# I2C-EXPANDER.net
KiCad netlist of a schematic drawn in Altium Designer
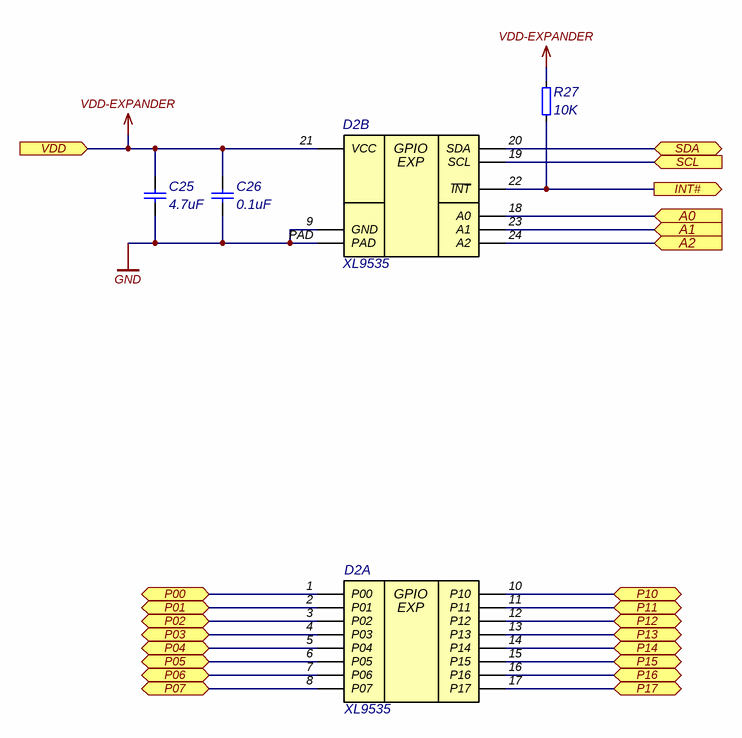
[diagram p0: I2C-EXPANDER.SchDoc]

(export (version "E")
  (design (tool "Eeschema 10.0.6"))
  (components
    (comp (ref "C25")
      (value "4.7uF")
      (footprint "C0402")
      (fields
        (field (name "PART NUMBER") "0402-X5R-6.3V-4.7uF±20%")
        (field (name "VOLTAGE") "6.3V")
        (field (name "TOLERANCE") "20%")
      )
      (libsource (lib "ATB") (part "C"))
    )
    (comp (ref "C26")
      (value "0.1uF")
      (footprint "C0402")
      (fields
        (field (name "PART NUMBER") "0402-X7R-16V-0.1uF±10%")
        (field (name "VOLTAGE") "16V")
        (field (name "TOLERANCE") "5%")
      )
      (libsource (lib "ATB") (part "C"))
    )
    (comp (ref "D2")
      (value "XL9535")
      (footprint "QFN_24_4X4_E0p5")
      (description "I2C  I/O Expander 16 bit")
      (fields (field (name "PART NUMBER") "XL9535QF24") (field (name "MANUFACTURER") "XINLUDA"))
      (libsource (lib "ATB") (part "XL95x5QF24"))
    )
    (comp (ref "R27")
      (value "10K")
      (footprint "R_0402")
      (fields
        (field (name "PART NUMBER") "0402-0.0625W-10K-100ppm±1%")
        (field (name "TOLERANCE") "1%")
        (field (name "MANUFACTURER") "Yageo")
      )
      (libsource (lib "ATB") (part "R"))
    )
  )
  (nets
    (net (code "1") (name "/A0") (class "Default")
      (node (ref "D2") (pin "18") (pinfunction "A0_18") (pintype "passive"))
    )
    (net (code "2") (name "/A1") (class "Default")
      (node (ref "D2") (pin "23") (pinfunction "A1_23") (pintype "passive"))
    )
    (net (code "3") (name "/A2") (class "Default")
      (node (ref "D2") (pin "24") (pinfunction "A2_24") (pintype "passive"))
    )
    (net (code "4") (name "/INT#") (class "Default")
      (node (ref "D2") (pin "22") (pinfunction "~{INT}_22") (pintype "passive"))
      (node (ref "R27") (pin "1") (pinfunction "1_1") (pintype "passive"))
    )
    (net (code "5") (name "/P00") (class "Default")
      (node (ref "D2") (pin "1") (pinfunction "P00_1") (pintype "passive"))
    )
    (net (code "6") (name "/P01") (class "Default")
      (node (ref "D2") (pin "2") (pinfunction "P01_2") (pintype "passive"))
    )
    (net (code "7") (name "/P02") (class "Default")
      (node (ref "D2") (pin "3") (pinfunction "P02_3") (pintype "passive"))
    )
    (net (code "8") (name "/P03") (class "Default")
      (node (ref "D2") (pin "4") (pinfunction "P03_4") (pintype "passive"))
    )
    (net (code "9") (name "/P04") (class "Default")
      (node (ref "D2") (pin "5") (pinfunction "P04_5") (pintype "passive"))
    )
    (net (code "10") (name "/P05") (class "Default")
      (node (ref "D2") (pin "6") (pinfunction "P05_6") (pintype "passive"))
    )
    (net (code "11") (name "/P06") (class "Default")
      (node (ref "D2") (pin "7") (pinfunction "P06_7") (pintype "passive"))
    )
    (net (code "12") (name "/P07") (class "Default")
      (node (ref "D2") (pin "8") (pinfunction "P07_8") (pintype "passive"))
    )
    (net (code "13") (name "/P10") (class "Default")
      (node (ref "D2") (pin "10") (pinfunction "P10_10") (pintype "passive"))
    )
    (net (code "14") (name "/P11") (class "Default")
      (node (ref "D2") (pin "11") (pinfunction "P11_11") (pintype "passive"))
    )
    (net (code "15") (name "/P12") (class "Default")
      (node (ref "D2") (pin "12") (pinfunction "P12_12") (pintype "passive"))
    )
    (net (code "16") (name "/P13") (class "Default")
      (node (ref "D2") (pin "13") (pinfunction "P13_13") (pintype "passive"))
    )
    (net (code "17") (name "/P14") (class "Default")
      (node (ref "D2") (pin "14") (pinfunction "P14_14") (pintype "passive"))
    )
    (net (code "18") (name "/P15") (class "Default")
      (node (ref "D2") (pin "15") (pinfunction "P15_15") (pintype "passive"))
    )
    (net (code "19") (name "/P16") (class "Default")
      (node (ref "D2") (pin "16") (pinfunction "P16_16") (pintype "passive"))
    )
    (net (code "20") (name "/P17") (class "Default")
      (node (ref "D2") (pin "17") (pinfunction "P17_17") (pintype "passive"))
    )
    (net (code "21") (name "/SCL") (class "Default")
      (node (ref "D2") (pin "19") (pinfunction "SCL_19") (pintype "passive"))
    )
    (net (code "22") (name "/SDA") (class "Default")
      (node (ref "D2") (pin "20") (pinfunction "SDA_20") (pintype "passive"))
    )
    (net (code "23") (name "GND") (class "Default")
      (node (ref "C25") (pin "1") (pinfunction "1_1") (pintype "passive"))
      (node (ref "C26") (pin "1") (pinfunction "1_1") (pintype "passive"))
      (node (ref "D2") (pin "9") (pinfunction "GND_9") (pintype "passive"))
      (node (ref "D2") (pin "PAD") (pinfunction "PAD_PAD") (pintype "passive"))
    )
    (net (code "24") (name "VDD-EXPANDER") (class "Default")
      (node (ref "C25") (pin "2") (pinfunction "2_2") (pintype "passive"))
      (node (ref "C26") (pin "2") (pinfunction "2_2") (pintype "passive"))
      (node (ref "D2") (pin "21") (pinfunction "VCC_21") (pintype "passive"))
      (node (ref "R27") (pin "2") (pinfunction "2_2") (pintype "passive"))
    )
  )
)
